# Tempy.net
KiCad netlist of a schematic drawn in EAGLE
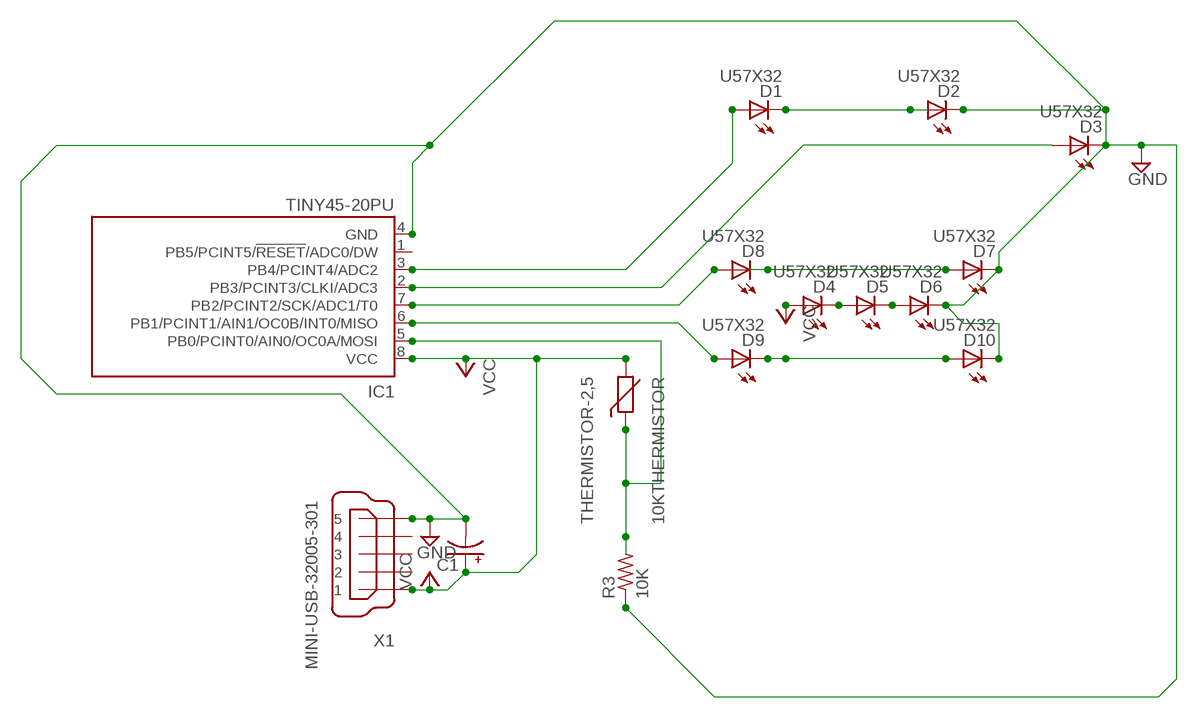
[diagram p0: schematic, sheet 1]

(export (version "E")
  (design (tool "Eeschema 10.0.6"))
  (components
    (comp (ref "10KTHERMISTOR")
      (value "THERMISTOR-2,5")
      (footprint "eagle-import:RS-2,5")
      (libsource (lib "eagle-import") (part "THERMISTOR-2,5"))
    )
    (comp (ref "C1")
      (value "CPOL-USE5-4")
      (footprint "eagle-import:E5-4")
      (libsource (lib "eagle-import") (part "CPOL-USE5-4"))
    )
    (comp (ref "D1")
      (value "U57X32")
      (footprint "eagle-import:U57X32")
      (libsource (lib "eagle-import") (part "U57X32"))
    )
    (comp (ref "D2")
      (value "U57X32")
      (footprint "eagle-import:U57X32")
      (libsource (lib "eagle-import") (part "U57X32"))
    )
    (comp (ref "D3")
      (value "U57X32")
      (footprint "eagle-import:U57X32")
      (libsource (lib "eagle-import") (part "U57X32"))
    )
    (comp (ref "D4")
      (value "U57X32")
      (footprint "eagle-import:U57X32")
      (libsource (lib "eagle-import") (part "U57X32"))
    )
    (comp (ref "D5")
      (value "U57X32")
      (footprint "eagle-import:U57X32")
      (libsource (lib "eagle-import") (part "U57X32"))
    )
    (comp (ref "D6")
      (value "U57X32")
      (footprint "eagle-import:U57X32")
      (libsource (lib "eagle-import") (part "U57X32"))
    )
    (comp (ref "D7")
      (value "U57X32")
      (footprint "eagle-import:U57X32")
      (libsource (lib "eagle-import") (part "U57X32"))
    )
    (comp (ref "D8")
      (value "U57X32")
      (footprint "eagle-import:U57X32")
      (libsource (lib "eagle-import") (part "U57X32"))
    )
    (comp (ref "D9")
      (value "U57X32")
      (footprint "eagle-import:U57X32")
      (libsource (lib "eagle-import") (part "U57X32"))
    )
    (comp (ref "D10")
      (value "U57X32")
      (footprint "eagle-import:U57X32")
      (libsource (lib "eagle-import") (part "U57X32"))
    )
    (comp (ref "IC1")
      (value "TINY45-20PU")
      (footprint "eagle-import:DIL08")
      (fields (field (name "MPN") "ATTINY13-20PU"))
      (libsource (lib "eagle-import") (part "TINY13PU-20"))
    )
    (comp (ref "R3")
      (value "10K")
      (footprint "eagle-import:0204_7")
      (libsource (lib "eagle-import") (part "R-US_0204/7"))
    )
    (comp (ref "X1")
      (value "MINI-USB-32005-301")
      (footprint "eagle-import:32005-301")
      (libsource (lib "eagle-import") (part "MINI-USB-32005-301"))
    )
  )
  (nets
    (net (code "1") (name "GND") (class "Default")
      (node (ref "C1") (pin "-") (pinfunction "-_-") (pintype "passive"))
      (node (ref "D10") (pin "K") (pinfunction "C_K") (pintype "passive"))
      (node (ref "D2") (pin "K") (pinfunction "C_K") (pintype "passive"))
      (node (ref "D3") (pin "K") (pinfunction "C_K") (pintype "passive"))
      (node (ref "D6") (pin "K") (pinfunction "C_K") (pintype "passive"))
      (node (ref "D7") (pin "K") (pinfunction "C_K") (pintype "passive"))
      (node (ref "IC1") (pin "4") (pinfunction "GND_4") (pintype "power_in"))
      (node (ref "R3") (pin "1") (pinfunction "1_1") (pintype "passive"))
      (node (ref "X1") (pin "5") (pinfunction "5_5") (pintype "passive"))
    )
    (net (code "2") (name "Net-(D1-C)") (class "Default")
      (node (ref "D1") (pin "K") (pinfunction "C_K") (pintype "passive"))
      (node (ref "D2") (pin "A") (pinfunction "A_A") (pintype "passive"))
    )
    (net (code "3") (name "Net-(D4-C)") (class "Default")
      (node (ref "D4") (pin "K") (pinfunction "C_K") (pintype "passive"))
      (node (ref "D5") (pin "A") (pinfunction "A_A") (pintype "passive"))
    )
    (net (code "4") (name "Net-(D5-C)") (class "Default")
      (node (ref "D5") (pin "K") (pinfunction "C_K") (pintype "passive"))
      (node (ref "D6") (pin "A") (pinfunction "A_A") (pintype "passive"))
    )
    (net (code "5") (name "Net-(D8-C)") (class "Default")
      (node (ref "D7") (pin "A") (pinfunction "A_A") (pintype "passive"))
      (node (ref "D8") (pin "K") (pinfunction "C_K") (pintype "passive"))
    )
    (net (code "6") (name "Net-(D9-C)") (class "Default")
      (node (ref "D10") (pin "A") (pinfunction "A_A") (pintype "passive"))
      (node (ref "D9") (pin "K") (pinfunction "C_K") (pintype "passive"))
    )
    (net (code "7") (name "Net-(IC1-PB0{slash}PCINT0{slash}AIN0{slash}OC0A{slash}MOSI)") (class "Default")
      (node (ref "10KTHERMISTOR") (pin "1") (pinfunction "1_1") (pintype "passive"))
      (node (ref "IC1") (pin "5") (pinfunction "PB0/PCINT0/AIN0/OC0A/MOSI_5") (pintype "bidirectional"))
      (node (ref "R3") (pin "2") (pinfunction "2_2") (pintype "passive"))
    )
    (net (code "8") (name "Net-(IC1-PB1{slash}PCINT1{slash}AIN1{slash}OC0B{slash}INT0{slash}MISO)") (class "Default")
      (node (ref "D9") (pin "A") (pinfunction "A_A") (pintype "passive"))
      (node (ref "IC1") (pin "6") (pinfunction "PB1/PCINT1/AIN1/OC0B/INT0/MISO_6") (pintype "bidirectional"))
    )
    (net (code "9") (name "Net-(IC1-PB2{slash}PCINT2{slash}SCK{slash}ADC1{slash}T0)") (class "Default")
      (node (ref "D8") (pin "A") (pinfunction "A_A") (pintype "passive"))
      (node (ref "IC1") (pin "7") (pinfunction "PB2/PCINT2/SCK/ADC1/T0_7") (pintype "bidirectional"))
    )
    (net (code "10") (name "Net-(IC1-PB3{slash}PCINT3{slash}CLKI{slash}ADC3)") (class "Default")
      (node (ref "D3") (pin "A") (pinfunction "A_A") (pintype "passive"))
      (node (ref "IC1") (pin "2") (pinfunction "PB3/PCINT3/CLKI/ADC3_2") (pintype "bidirectional"))
    )
    (net (code "11") (name "Net-(IC1-PB4{slash}PCINT4{slash}ADC2)") (class "Default")
      (node (ref "D1") (pin "A") (pinfunction "A_A") (pintype "passive"))
      (node (ref "IC1") (pin "3") (pinfunction "PB4/PCINT4/ADC2_3") (pintype "bidirectional"))
    )
    (net (code "12") (name "VCC") (class "Default")
      (node (ref "10KTHERMISTOR") (pin "2") (pinfunction "2_2") (pintype "passive"))
      (node (ref "C1") (pin "+") (pinfunction "+_+") (pintype "passive"))
      (node (ref "D4") (pin "A") (pinfunction "A_A") (pintype "passive"))
      (node (ref "IC1") (pin "8") (pinfunction "VCC_8") (pintype "power_in"))
      (node (ref "X1") (pin "1") (pinfunction "1_1") (pintype "passive"))
    )
    (net (code "13") (name "unconnected-(IC1-PB5{slash}PCINT5{slash}~{RESET}{slash}ADC0{slash}DW-Pad1)") (class "Default")
      (node (ref "IC1") (pin "1") (pinfunction "PB5/PCINT5/~{RESET}/ADC0/DW_1") (pintype "bidirectional"))
    )
    (net (code "14") (name "unconnected-(X1-Pad2)") (class "Default")
      (node (ref "X1") (pin "2") (pinfunction "2_2") (pintype "passive"))
    )
    (net (code "15") (name "unconnected-(X1-Pad3)") (class "Default")
      (node (ref "X1") (pin "3") (pinfunction "3_3") (pintype "passive"))
    )
    (net (code "16") (name "unconnected-(X1-Pad4)") (class "Default")
      (node (ref "X1") (pin "4") (pinfunction "4_4") (pintype "passive"))
    )
  )
)
